# rapidshark-pmos-quarter-bridge-mk-1_0.net
KiCad netlist of a schematic drawn in EAGLE
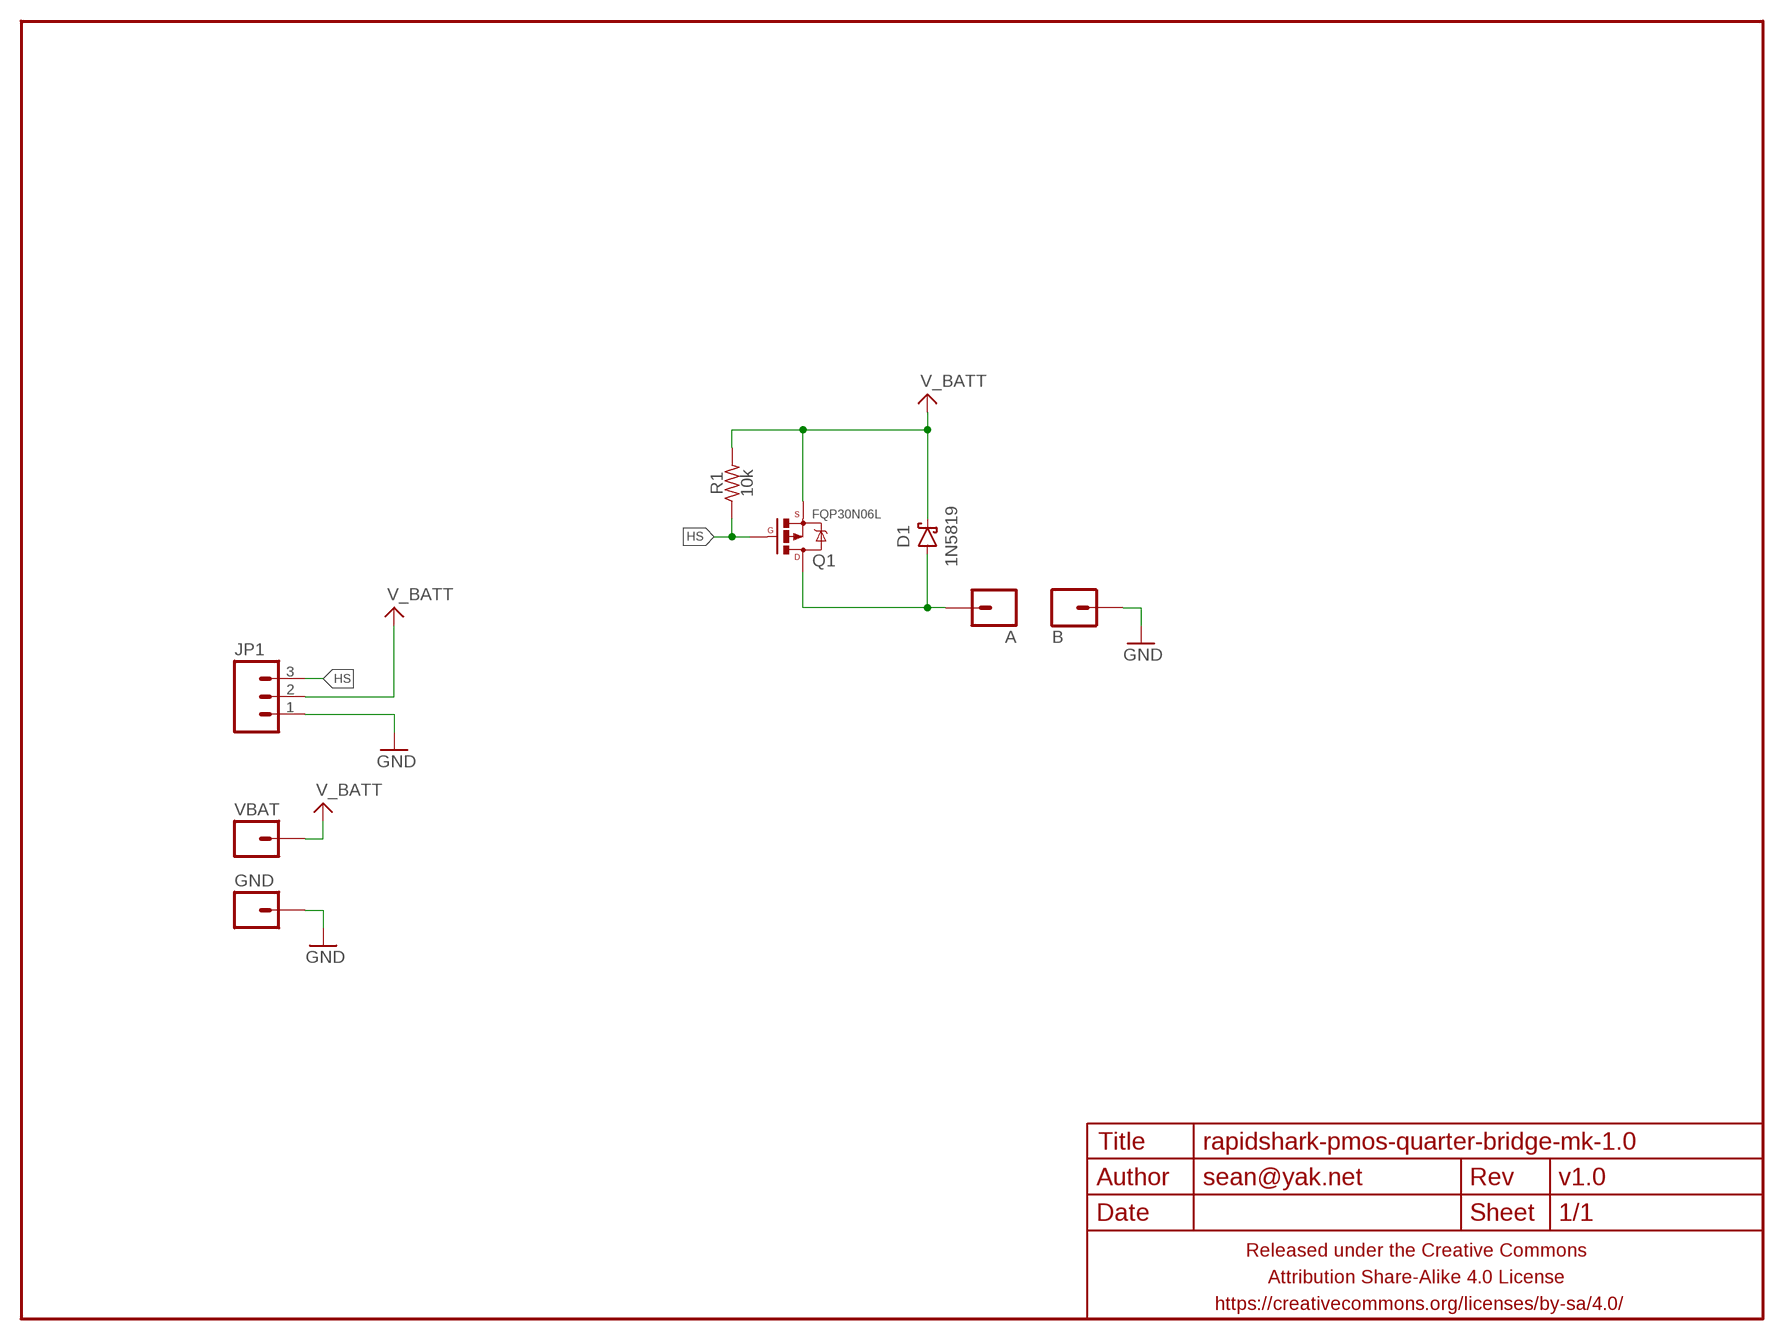
[diagram p0: schematic, sheet 1]

(export (version "E")
  (design (tool "Eeschema 10.0.6"))
  (components
    (comp (ref "A")
      (value "M0112AWG")
      (footprint "eagle-import:1X01-12AWG")
      (libsource (lib "eagle-import") (part "M0112AWG"))
    )
    (comp (ref "B")
      (value "M0112AWG")
      (footprint "eagle-import:1X01-12AWG")
      (libsource (lib "eagle-import") (part "M0112AWG"))
    )
    (comp (ref "D1")
      (value "1N5819")
      (footprint "eagle-import:DIODE-SCHOTTKY-10.16MM")
      (libsource (lib "eagle-import") (part "DIODE-SCHOTTKYPTH-10.16MM"))
    )
    (comp (ref "FRAME1")
      (value "FRAME-LETTERNO_PACKAGE")
      (footprint "eagle-import:DUMMY")
      (fields (field (name "DESIGNER") "sean@yak.net") (field (name "VERSION") "v1.0"))
      (libsource (lib "eagle-import") (part "FRAME-LETTERNO_PACKAGE"))
    )
    (comp (ref "GND")
      (value "M0112AWG")
      (footprint "eagle-import:1X01-12AWG")
      (libsource (lib "eagle-import") (part "M0112AWG"))
    )
    (comp (ref "JP1")
      (value "M03PTH-CENTERED")
      (footprint "eagle-import:1X03-CENTERED")
      (libsource (lib "eagle-import") (part "M03PTH-CENTERED"))
    )
    (comp (ref "Q1")
      (value "FQP30N06L")
      (footprint "eagle-import:TO220-THERMPAD")
      (libsource (lib "eagle-import") (part "MOSFET-PCHANNELTO-220-THERMPAD-TABONLY"))
    )
    (comp (ref "R1")
      (value "10k")
      (footprint "eagle-import:RESISTOR-AXIAL-PTH-5.08MM")
      (libsource (lib "eagle-import") (part "RESISTORPTH-AXIAL-5.08MM"))
    )
    (comp (ref "VBAT")
      (value "M0112AWG")
      (footprint "eagle-import:1X01-12AWG")
      (libsource (lib "eagle-import") (part "M0112AWG"))
    )
  )
  (nets
    (net (code "1") (name "GND") (class "Default")
      (node (ref "B") (pin "1") (pinfunction "1_1") (pintype "passive"))
      (node (ref "GND") (pin "1") (pinfunction "1_1") (pintype "passive"))
      (node (ref "JP1") (pin "1") (pinfunction "1_1") (pintype "passive"))
    )
    (net (code "2") (name "HS") (class "Default")
      (node (ref "JP1") (pin "3") (pinfunction "3_3") (pintype "passive"))
      (node (ref "Q1") (pin "1") (pinfunction "G_1") (pintype "passive"))
      (node (ref "R1") (pin "P$1") (pinfunction "1_P$1") (pintype "passive"))
    )
    (net (code "3") (name "Net-(Q1-D)") (class "Default")
      (node (ref "A") (pin "1") (pinfunction "1_1") (pintype "passive"))
      (node (ref "D1") (pin "A") (pinfunction "A_A") (pintype "passive"))
      (node (ref "Q1") (pin "2@1") (pinfunction "D_2@1") (pintype "passive"))
    )
    (net (code "4") (name "V_BATT") (class "Default")
      (node (ref "D1") (pin "C") (pinfunction "C_C") (pintype "passive"))
      (node (ref "JP1") (pin "2") (pinfunction "2_2") (pintype "passive"))
      (node (ref "Q1") (pin "3") (pinfunction "S_3") (pintype "passive"))
      (node (ref "R1") (pin "P$2") (pinfunction "2_P$2") (pintype "passive"))
      (node (ref "VBAT") (pin "1") (pinfunction "1_1") (pintype "passive"))
    )
  )
)
